# 12-I225_1.net
KiCad netlist of a schematic drawn in Altium Designer
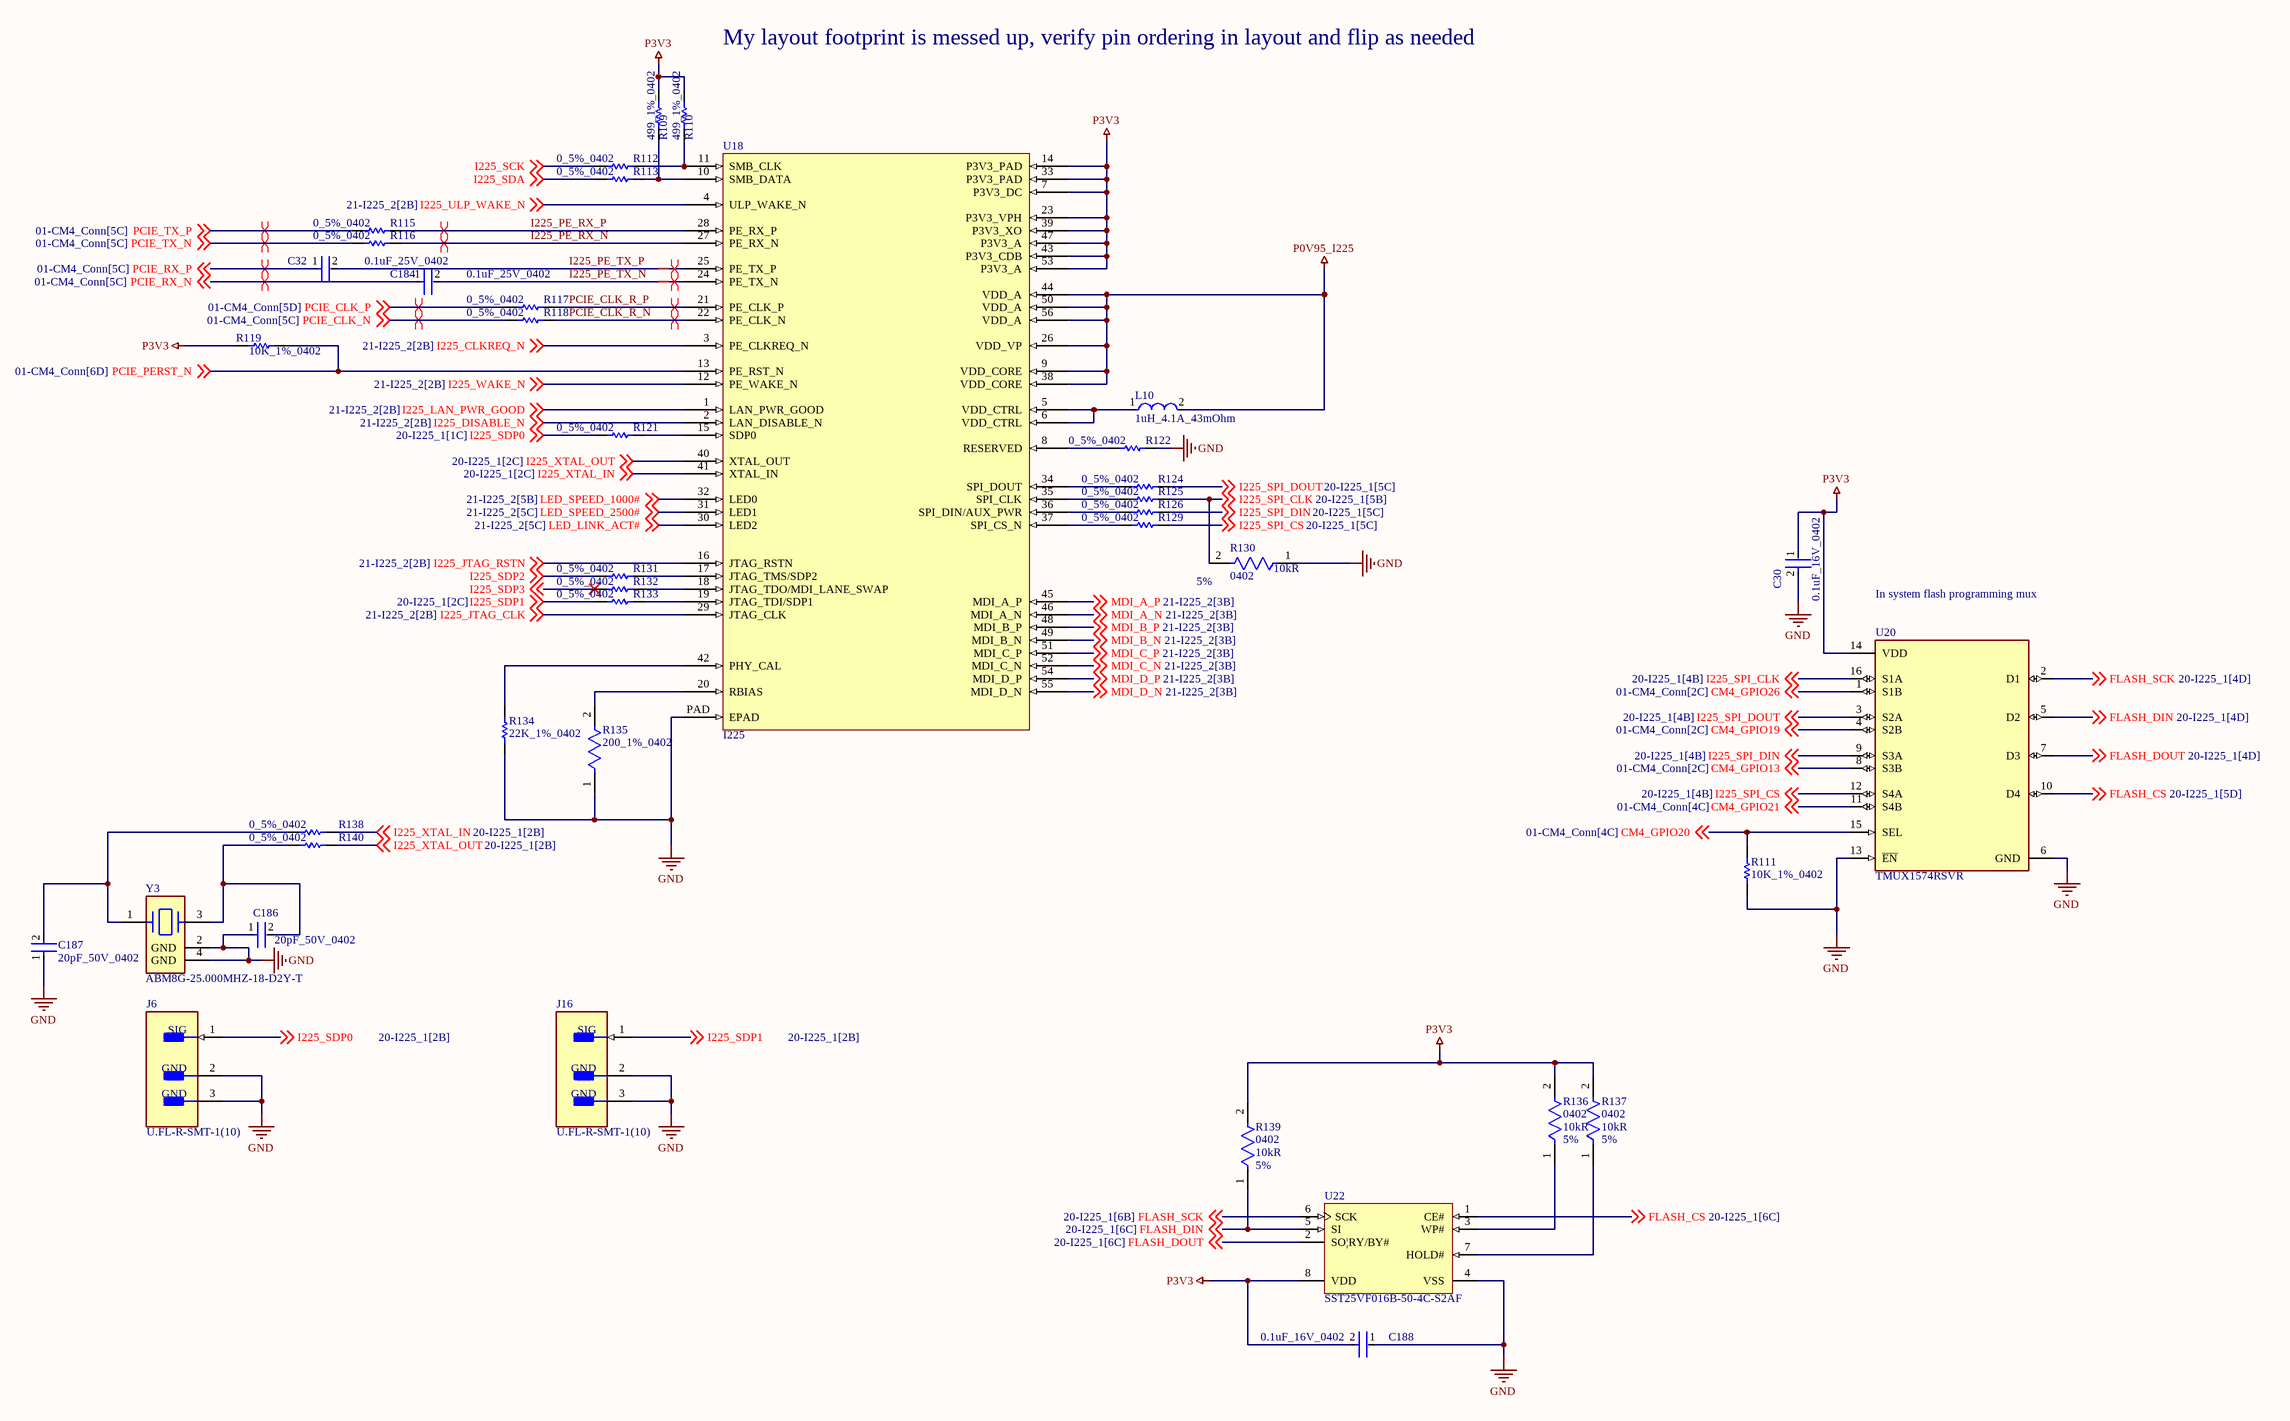
[diagram p0: 12-I225_1.SchDoc]

(export (version "E")
  (design (tool "Eeschema 10.0.6"))
  (components
    (comp (ref "C30")
      (value "0.1uF_16V_0402")
      (footprint "FP-GRM15-MFG")
      (description "CAP CER 0.1UF 16V X7R 0402")
      (fields (field (name "MANUFACTURER PART NUMBER") "GRM155R71C104KA88D") (field (name "TOLERANCE") "10%"))
      (libsource (lib "Altium Content Vault") (part "236180d848d6139a670b325ea6854c9"))
    )
    (comp (ref "C32")
      (value "0.1uF_25V_0402")
      (footprint "FP-0402-L_1_0_1-W_0_5_0_1-IPC_C")
      (description "General Purpose Ceramic Capacitor, 0402, 100nF, 10%, X7R, 15%, 25V")
      (fields (field (name "VOLTAGE") "25V") (field (name "TOLERANCE") "10%"))
      (libsource (lib "Altium Content Vault") (part "b4654b650e69147ec39a6b967a45e02"))
    )
    (comp (ref "C184")
      (value "0.1uF_25V_0402")
      (footprint "FP-0402-L_1_0_1-W_0_5_0_1-IPC_C")
      (description "General Purpose Ceramic Capacitor, 0402, 100nF, 10%, X7R, 15%, 25V")
      (fields (field (name "VOLTAGE") "25V") (field (name "TOLERANCE") "10%"))
      (libsource (lib "Altium Content Vault") (part "b4654b650e69147ec39a6b967a45e02"))
    )
    (comp (ref "C186")
      (value "20pF_50V_0402")
      (footprint "FP-C0402-BB-MFG")
      (description "CAP CER 20PF 50V 5% NP0 0402")
      (fields
        (field (name "MANUFACTURER PART NUMBER") "C0402C200J5GACTU")
        (field (name "OCTOPART") "https://octopart.com/c0402c200j5gactu-kemet-9143900")
      )
      (libsource (lib "Altium Content Vault") (part "b4654b650e69147ec39a6b967a45e02"))
    )
    (comp (ref "C187")
      (value "20pF_50V_0402")
      (footprint "FP-C0402-BB-MFG")
      (description "CAP CER 20PF 50V 5% NP0 0402")
      (fields
        (field (name "MANUFACTURER PART NUMBER") "C0402C200J5GACTU")
        (field (name "OCTOPART") "https://octopart.com/c0402c200j5gactu-kemet-9143900")
      )
      (libsource (lib "Altium Content Vault") (part "b4654b650e69147ec39a6b967a45e02"))
    )
    (comp (ref "C188")
      (value "0.1uF_16V_0402")
      (footprint "FP-GRM15-MFG")
      (description "CAP CER 0.1UF 16V X7R 0402")
      (fields (field (name "MANUFACTURER PART NUMBER") "GRM155R71C104KA88D") (field (name "TOLERANCE") "10%"))
      (libsource (lib "Altium Content Vault") (part "236180d848d6139a670b325ea6854c9"))
    )
    (comp (ref "J6")
      (value "U.FL-R-SMT-1(10)")
      (footprint "FP-U_FL-R-SMT-1_10-MFG")
      (description "CONN U.FL RCPT STR 50 OHM SMD")
      (libsource (lib "Altium Content Vault") (part "7158abf7d987fa84906f6fb0d115710"))
    )
    (comp (ref "J16")
      (value "U.FL-R-SMT-1(10)")
      (footprint "FP-U_FL-R-SMT-1_10-MFG")
      (description "CONN U.FL RCPT STR 50 OHM SMD")
      (libsource (lib "Altium Content Vault") (part "7158abf7d987fa84906f6fb0d115710"))
    )
    (comp (ref "L10")
      (value "1uH_4.1A_43mOhm")
      (footprint "FP-CIGT201610-MFG")
      (description "FIXED IND 1UH 4.1A 43 MOHM SMD")
      (fields (field (name "TOLERANCE") "20%"))
      (libsource (lib "Altium Content Vault") (part "725321dda6339637d4d059423bc1c3c"))
    )
    (comp (ref "R109")
      (value "499_1%_0402")
      (footprint "RESC1005X40X25LL05T05")
      (fields (field (name "MANUFACTURER") "Panasonic") (field (name "PART NUMBER") "ERJ-2RKF4990X"))
      (libsource (lib "Altium Content Vault") (part "RES"))
    )
    (comp (ref "R110")
      (value "499_1%_0402")
      (footprint "RESC1005X40X25LL05T05")
      (fields (field (name "MANUFACTURER") "Panasonic") (field (name "PART NUMBER") "ERJ-2RKF4990X"))
      (libsource (lib "Altium Content Vault") (part "RES"))
    )
    (comp (ref "R111")
      (value "10K_1%_0402")
      (footprint "RESC1005X40X25NL10T10")
      (fields (field (name "MANUFACTURER") "Bourns") (field (name "PART NUMBER") "CR0402-FX-1002GLF"))
      (libsource (lib "Altium Content Vault") (part "RES"))
    )
    (comp (ref "R112")
      (value "0_5%_0402")
      (footprint "RESC1005X40X25LL10T10")
      (fields (field (name "MANUFACTURER") "KOA Speer") (field (name "PART NUMBER") "RK73Z1ETTP"))
      (libsource (lib "Altium Content Vault") (part "RES"))
    )
    (comp (ref "R113")
      (value "0_5%_0402")
      (footprint "RESC1005X40X25LL10T10")
      (fields (field (name "MANUFACTURER") "KOA Speer") (field (name "PART NUMBER") "RK73Z1ETTP"))
      (libsource (lib "Altium Content Vault") (part "RES"))
    )
    (comp (ref "R115")
      (value "0_5%_0402")
      (footprint "RESC1005X40X25LL10T10")
      (fields (field (name "MANUFACTURER") "KOA Speer") (field (name "PART NUMBER") "RK73Z1ETTP"))
      (libsource (lib "Altium Content Vault") (part "RES"))
    )
    (comp (ref "R116")
      (value "0_5%_0402")
      (footprint "RESC1005X40X25LL10T10")
      (fields (field (name "MANUFACTURER") "KOA Speer") (field (name "PART NUMBER") "RK73Z1ETTP"))
      (libsource (lib "Altium Content Vault") (part "RES"))
    )
    (comp (ref "R117")
      (value "0_5%_0402")
      (footprint "RESC1005X40X25LL10T10")
      (fields (field (name "MANUFACTURER") "KOA Speer") (field (name "PART NUMBER") "RK73Z1ETTP"))
      (libsource (lib "Altium Content Vault") (part "RES"))
    )
    (comp (ref "R118")
      (value "0_5%_0402")
      (footprint "RESC1005X40X25LL10T10")
      (fields (field (name "MANUFACTURER") "KOA Speer") (field (name "PART NUMBER") "RK73Z1ETTP"))
      (libsource (lib "Altium Content Vault") (part "RES"))
    )
    (comp (ref "R119")
      (value "10K_1%_0402")
      (footprint "RESC1005X40X25NL10T10")
      (fields (field (name "MANUFACTURER") "Bourns") (field (name "PART NUMBER") "CR0402-FX-1002GLF"))
      (libsource (lib "Altium Content Vault") (part "RES"))
    )
    (comp (ref "R121")
      (value "0_5%_0402")
      (footprint "RESC1005X40X25LL10T10")
      (fields (field (name "MANUFACTURER") "KOA Speer") (field (name "PART NUMBER") "RK73Z1ETTP"))
      (libsource (lib "Altium Content Vault") (part "RES"))
    )
    (comp (ref "R122")
      (value "0_5%_0402")
      (footprint "RESC1005X40X25LL10T10")
      (fields (field (name "MANUFACTURER") "KOA Speer") (field (name "PART NUMBER") "RK73Z1ETTP"))
      (libsource (lib "Altium Content Vault") (part "RES"))
    )
    (comp (ref "R124")
      (value "0_5%_0402")
      (footprint "RESC1005X40X25LL10T10")
      (fields (field (name "MANUFACTURER") "KOA Speer") (field (name "PART NUMBER") "RK73Z1ETTP"))
      (libsource (lib "Altium Content Vault") (part "RES"))
    )
    (comp (ref "R125")
      (value "0_5%_0402")
      (footprint "RESC1005X40X25LL10T10")
      (fields (field (name "MANUFACTURER") "KOA Speer") (field (name "PART NUMBER") "RK73Z1ETTP"))
      (libsource (lib "Altium Content Vault") (part "RES"))
    )
    (comp (ref "R126")
      (value "0_5%_0402")
      (footprint "RESC1005X40X25LL10T10")
      (fields (field (name "MANUFACTURER") "KOA Speer") (field (name "PART NUMBER") "RK73Z1ETTP"))
      (libsource (lib "Altium Content Vault") (part "RES"))
    )
    (comp (ref "R129")
      (value "0_5%_0402")
      (footprint "RESC1005X40X25LL10T10")
      (fields (field (name "MANUFACTURER") "KOA Speer") (field (name "PART NUMBER") "RK73Z1ETTP"))
      (libsource (lib "Altium Content Vault") (part "RES"))
    )
    (comp (ref "R130")
      (value "CRCW040210K0JNED")
      (footprint "FP-CRCW0402-e3-IPC_B")
      (description "RES Thick Film, 10kΩ, 5%, 0.063W, 200ppm/°C, 0402")
      (fields
        (field (name "CASE/PACKAGE") "0402")
        (field (name "RESISTANCE") "10kR")
        (field (name "TOLERANCE") "5%")
      )
      (libsource (lib "Altium Content Vault") (part "1029c3af85768c4190bb7ad29bc67b5"))
    )
    (comp (ref "R131")
      (value "0_5%_0402")
      (footprint "RESC1005X40X25LL10T10")
      (fields (field (name "MANUFACTURER") "KOA Speer") (field (name "PART NUMBER") "RK73Z1ETTP"))
      (libsource (lib "Altium Content Vault") (part "RES"))
    )
    (comp (ref "R132")
      (value "0_5%_0402")
      (footprint "RESC1005X40X25LL10T10")
      (fields (field (name "MANUFACTURER") "KOA Speer") (field (name "PART NUMBER") "RK73Z1ETTP"))
      (libsource (lib "Altium Content Vault") (part "RES"))
    )
    (comp (ref "R133")
      (value "0_5%_0402")
      (footprint "RESC1005X40X25LL10T10")
      (fields (field (name "MANUFACTURER") "KOA Speer") (field (name "PART NUMBER") "RK73Z1ETTP"))
      (libsource (lib "Altium Content Vault") (part "RES"))
    )
    (comp (ref "R134")
      (value "22K_1%_0402")
      (footprint "RESC1005X40X25NL05T05")
      (fields (field (name "PART NUMBER") "CRCW040222K0FKED") (field (name "MANUFACTURER") "Vishay Dale"))
      (libsource (lib "Altium Content Vault") (part "RES"))
    )
    (comp (ref "R135")
      (value "200_1%_0402")
      (footprint "FP-CRCW0402-e3-IPC_C")
      (description "RES Thick Film, 200Ω, 1%, 0.063W, 100ppm/°C, 0402")
      (fields (field (name "TOLERANCE") "1%"))
      (libsource (lib "Altium Content Vault") (part "1029c3af85768c4190bb7ad29bc67b5"))
    )
    (comp (ref "R136")
      (value "CRCW040210K0JNED")
      (footprint "FP-CRCW0402-e3-IPC_B")
      (description "RES Thick Film, 10kΩ, 5%, 0.063W, 200ppm/°C, 0402")
      (fields
        (field (name "CASE/PACKAGE") "0402")
        (field (name "RESISTANCE") "10kR")
        (field (name "TOLERANCE") "5%")
      )
      (libsource (lib "Altium Content Vault") (part "1029c3af85768c4190bb7ad29bc67b5"))
    )
    (comp (ref "R137")
      (value "CRCW040210K0JNED")
      (footprint "FP-CRCW0402-e3-IPC_B")
      (description "RES Thick Film, 10kΩ, 5%, 0.063W, 200ppm/°C, 0402")
      (fields
        (field (name "CASE/PACKAGE") "0402")
        (field (name "RESISTANCE") "10kR")
        (field (name "TOLERANCE") "5%")
      )
      (libsource (lib "Altium Content Vault") (part "1029c3af85768c4190bb7ad29bc67b5"))
    )
    (comp (ref "R138")
      (value "0_5%_0402")
      (footprint "RESC1005X40X25LL10T10")
      (fields (field (name "MANUFACTURER") "KOA Speer") (field (name "PART NUMBER") "RK73Z1ETTP"))
      (libsource (lib "Altium Content Vault") (part "RES"))
    )
    (comp (ref "R139")
      (value "CRCW040210K0JNED")
      (footprint "FP-CRCW0402-e3-IPC_B")
      (description "RES Thick Film, 10kΩ, 5%, 0.063W, 200ppm/°C, 0402")
      (fields
        (field (name "CASE/PACKAGE") "0402")
        (field (name "RESISTANCE") "10kR")
        (field (name "TOLERANCE") "5%")
      )
      (libsource (lib "Altium Content Vault") (part "1029c3af85768c4190bb7ad29bc67b5"))
    )
    (comp (ref "R140")
      (value "0_5%_0402")
      (footprint "RESC1005X40X25LL10T10")
      (fields (field (name "MANUFACTURER") "KOA Speer") (field (name "PART NUMBER") "RK73Z1ETTP"))
      (libsource (lib "Altium Content Vault") (part "RES"))
    )
    (comp (ref "U18") (value "I225") (footprint "I225 QFN56") (libsource (lib "TimeStick_Lib") (part "I225")))
    (comp (ref "U20")
      (value "TMUX1574RSVR")
      (footprint "FP-RSV0016A-MFG")
      (description "IC SWITCH SPDT QUAD 16UQFN")
      (libsource (lib "Altium Content Vault") (part "6ae91f3a9e3ea7621a49082f656dcdc"))
    )
    (comp (ref "U22")
      (value "SST25VF016B-50-4C-S2AF")
      (footprint "MCHP-SOIC-S2A8_M")
      (description "16 Mbit SPI Serial Flash, 2.7 to 3.6 V, 50 MHz, 0 to 70 degC, 8-pin SOIC (S2A8), Tube")
      (fields (field (name "MANUFACTURER") "Microchip"))
      (libsource (lib "Altium Content Vault") (part "MCHP-SST25VFXXXB-SOIX-8"))
    )
    (comp (ref "Y3")
      (value "ABM8G-25.000MHZ-18-D2Y-T")
      (footprint "FP-ABM8G-MFG")
      (description "CRYSTAL 25.0000MHZ 18PF SMD")
      (fields
        (field (name "MANUFACTURER") "Abracon")
        (field (name "OCTOPART") "https://octopart.com/abm8g-25.000mhz-18-d2y-t-abracon-12676602")
      )
      (libsource (lib "Altium Content Vault") (part "82af6c543cb7a88a4cbd02a3a01c293"))
    )
  )
  (nets
    (net (code "1") (name "/I225_PE_RX_N") (class "Default")
      (node (ref "R116") (pin "2") (pinfunction "2_2") (pintype "passive"))
      (node (ref "U18") (pin "27") (pinfunction "PE_RX_N_27") (pintype "input"))
    )
    (net (code "2") (name "/I225_PE_RX_P") (class "Default")
      (node (ref "R115") (pin "2") (pinfunction "2_2") (pintype "passive"))
      (node (ref "U18") (pin "28") (pinfunction "PE_RX_P_28") (pintype "input"))
    )
    (net (code "3") (name "/I225_PE_TX_N") (class "Default")
      (node (ref "C184") (pin "2") (pinfunction "2_2") (pintype "passive"))
      (node (ref "U18") (pin "24") (pinfunction "PE_TX_N_24") (pintype "input"))
    )
    (net (code "4") (name "/I225_PE_TX_P") (class "Default")
      (node (ref "C32") (pin "2") (pinfunction "2_2") (pintype "passive"))
      (node (ref "U18") (pin "25") (pinfunction "PE_TX_P_25") (pintype "input"))
    )
    (net (code "5") (name "/PCIE_CLK_R_N") (class "Default")
      (node (ref "R118") (pin "2") (pinfunction "2_2") (pintype "passive"))
      (node (ref "U18") (pin "22") (pinfunction "PE_CLK_N_22") (pintype "input"))
    )
    (net (code "6") (name "/PCIE_CLK_R_P") (class "Default")
      (node (ref "R117") (pin "2") (pinfunction "2_2") (pintype "passive"))
      (node (ref "U18") (pin "21") (pinfunction "PE_CLK_P_21") (pintype "input"))
    )
    (net (code "7") (name "CM4_GPIO13") (class "Default")
      (node (ref "U20") (pin "8") (pinfunction "S3B_8") (pintype "bidirectional"))
    )
    (net (code "8") (name "CM4_GPIO19") (class "Default")
      (node (ref "U20") (pin "4") (pinfunction "S2B_4") (pintype "bidirectional"))
    )
    (net (code "9") (name "CM4_GPIO20") (class "Default")
      (node (ref "R111") (pin "1") (pinfunction "1_1") (pintype "passive"))
      (node (ref "U20") (pin "15") (pinfunction "SEL_15") (pintype "input"))
    )
    (net (code "10") (name "CM4_GPIO21") (class "Default")
      (node (ref "U20") (pin "11") (pinfunction "S4B_11") (pintype "bidirectional"))
    )
    (net (code "11") (name "CM4_GPIO26") (class "Default")
      (node (ref "U20") (pin "1") (pinfunction "S1B_1") (pintype "bidirectional"))
    )
    (net (code "12") (name "FLASH_CS") (class "Default")
      (node (ref "U20") (pin "10") (pinfunction "D4_10") (pintype "bidirectional"))
      (node (ref "U22") (pin "1") (pinfunction "CE#_1") (pintype "input"))
    )
    (net (code "13") (name "FLASH_DIN") (class "Default")
      (node (ref "R139") (pin "1") (pinfunction "1_1") (pintype "passive"))
      (node (ref "U20") (pin "5") (pinfunction "D2_5") (pintype "bidirectional"))
      (node (ref "U22") (pin "5") (pinfunction "SI_5") (pintype "input"))
    )
    (net (code "14") (name "FLASH_DOUT") (class "Default")
      (node (ref "U20") (pin "7") (pinfunction "D3_7") (pintype "bidirectional"))
      (node (ref "U22") (pin "2") (pinfunction "SO¦RY/BY#_2") (pintype "tri_state"))
    )
    (net (code "15") (name "FLASH_SCK") (class "Default")
      (node (ref "U20") (pin "2") (pinfunction "D1_2") (pintype "bidirectional"))
      (node (ref "U22") (pin "6") (pinfunction "SCK_6") (pintype "input"))
    )
    (net (code "16") (name "GND") (class "Default")
      (node (ref "C186") (pin "1") (pinfunction "1_1") (pintype "passive"))
      (node (ref "C187") (pin "1") (pinfunction "1_1") (pintype "passive"))
      (node (ref "C188") (pin "1") (pinfunction "1_1") (pintype "passive"))
      (node (ref "C30") (pin "2") (pinfunction "2_2") (pintype "passive"))
      (node (ref "J16") (pin "2") (pinfunction "GND_2") (pintype "power_in"))
      (node (ref "J16") (pin "3") (pinfunction "GND_3") (pintype "power_in"))
      (node (ref "J6") (pin "2") (pinfunction "GND_2") (pintype "power_in"))
      (node (ref "J6") (pin "3") (pinfunction "GND_3") (pintype "power_in"))
      (node (ref "R111") (pin "2") (pinfunction "2_2") (pintype "passive"))
      (node (ref "R122") (pin "2") (pinfunction "2_2") (pintype "passive"))
      (node (ref "R130") (pin "1") (pinfunction "1_1") (pintype "passive"))
      (node (ref "R134") (pin "1") (pinfunction "1_1") (pintype "passive"))
      (node (ref "R135") (pin "1") (pinfunction "1_1") (pintype "passive"))
      (node (ref "U18") (pin "PAD") (pinfunction "EPAD_PAD") (pintype "input"))
      (node (ref "U20") (pin "13") (pinfunction "~{EN}_13") (pintype "input"))
      (node (ref "U20") (pin "6") (pinfunction "GND_6") (pintype "power_in"))
      (node (ref "U22") (pin "4") (pinfunction "VSS_4") (pintype "power_in"))
      (node (ref "Y3") (pin "2") (pinfunction "GND_2") (pintype "power_in"))
      (node (ref "Y3") (pin "4") (pinfunction "GND_4") (pintype "power_in"))
    )
    (net (code "17") (name "I225_CLKREQ_N") (class "Default")
      (node (ref "U18") (pin "3") (pinfunction "PE_CLKREQ_N_3") (pintype "input"))
    )
    (net (code "18") (name "I225_DISABLE_N") (class "Default")
      (node (ref "U18") (pin "2") (pinfunction "LAN_DISABLE_N_2") (pintype "input"))
    )
    (net (code "19") (name "I225_JTAG_CLK") (class "Default")
      (node (ref "U18") (pin "29") (pinfunction "JTAG_CLK_29") (pintype "input"))
    )
    (net (code "20") (name "I225_JTAG_RSTN") (class "Default")
      (node (ref "U18") (pin "16") (pinfunction "JTAG_RSTN_16") (pintype "input"))
    )
    (net (code "21") (name "I225_LAN_PWR_GOOD") (class "Default")
      (node (ref "U18") (pin "1") (pinfunction "LAN_PWR_GOOD_1") (pintype "input"))
    )
    (net (code "22") (name "I225_SCK") (class "Default")
      (node (ref "R112") (pin "1") (pinfunction "1_1") (pintype "passive"))
    )
    (net (code "23") (name "I225_SDA") (class "Default")
      (node (ref "R113") (pin "1") (pinfunction "1_1") (pintype "passive"))
    )
    (net (code "24") (name "I225_SDP0") (class "Default")
      (node (ref "J6") (pin "1") (pinfunction "SIG_1") (pintype "input"))
      (node (ref "R121") (pin "1") (pinfunction "1_1") (pintype "passive"))
    )
    (net (code "25") (name "I225_SDP1") (class "Default")
      (node (ref "J16") (pin "1") (pinfunction "SIG_1") (pintype "input"))
      (node (ref "R133") (pin "1") (pinfunction "1_1") (pintype "passive"))
    )
    (net (code "26") (name "I225_SDP2") (class "Default")
      (node (ref "R131") (pin "1") (pinfunction "1_1") (pintype "passive"))
    )
    (net (code "27") (name "I225_SDP3") (class "Default")
      (node (ref "R132") (pin "1") (pinfunction "1_1") (pintype "passive"))
    )
    (net (code "28") (name "I225_SPI_CLK") (class "Default")
      (node (ref "R125") (pin "2") (pinfunction "2_2") (pintype "passive"))
      (node (ref "R130") (pin "2") (pinfunction "2_2") (pintype "passive"))
      (node (ref "U20") (pin "16") (pinfunction "S1A_16") (pintype "bidirectional"))
    )
    (net (code "29") (name "I225_SPI_CS") (class "Default")
      (node (ref "R129") (pin "2") (pinfunction "2_2") (pintype "passive"))
      (node (ref "U20") (pin "12") (pinfunction "S4A_12") (pintype "bidirectional"))
    )
    (net (code "30") (name "I225_SPI_DIN") (class "Default")
      (node (ref "R126") (pin "2") (pinfunction "2_2") (pintype "passive"))
      (node (ref "U20") (pin "9") (pinfunction "S3A_9") (pintype "bidirectional"))
    )
    (net (code "31") (name "I225_SPI_DOUT") (class "Default")
      (node (ref "R124") (pin "2") (pinfunction "2_2") (pintype "passive"))
      (node (ref "U20") (pin "3") (pinfunction "S2A_3") (pintype "bidirectional"))
    )
    (net (code "32") (name "I225_ULP_WAKE_N") (class "Default")
      (node (ref "U18") (pin "4") (pinfunction "ULP_WAKE_N_4") (pintype "input"))
    )
    (net (code "33") (name "I225_WAKE_N") (class "Default")
      (node (ref "U18") (pin "12") (pinfunction "PE_WAKE_N_12") (pintype "input"))
    )
    (net (code "34") (name "I225_XTAL_IN") (class "Default")
      (node (ref "R138") (pin "2") (pinfunction "2_2") (pintype "passive"))
      (node (ref "U18") (pin "41") (pinfunction "XTAL_IN_41") (pintype "input"))
    )
    (net (code "35") (name "I225_XTAL_OUT") (class "Default")
      (node (ref "R140") (pin "2") (pinfunction "2_2") (pintype "passive"))
      (node (ref "U18") (pin "40") (pinfunction "XTAL_OUT_40") (pintype "input"))
    )
    (net (code "36") (name "LED_LINK_ACT#") (class "Default")
      (node (ref "U18") (pin "30") (pinfunction "LED2_30") (pintype "input"))
    )
    (net (code "37") (name "LED_SPEED_1000#") (class "Default")
      (node (ref "U18") (pin "32") (pinfunction "LED0_32") (pintype "input"))
    )
    (net (code "38") (name "LED_SPEED_2500#") (class "Default")
      (node (ref "U18") (pin "31") (pinfunction "LED1_31") (pintype "input"))
    )
    (net (code "39") (name "MDI_A_N") (class "Default")
      (node (ref "U18") (pin "46") (pinfunction "MDI_A_N_46") (pintype "input"))
    )
    (net (code "40") (name "MDI_A_P") (class "Default")
      (node (ref "U18") (pin "45") (pinfunction "MDI_A_P_45") (pintype "input"))
    )
    (net (code "41") (name "MDI_B_N") (class "Default")
      (node (ref "U18") (pin "49") (pinfunction "MDI_B_N_49") (pintype "input"))
    )
    (net (code "42") (name "MDI_B_P") (class "Default")
      (node (ref "U18") (pin "48") (pinfunction "MDI_B_P_48") (pintype "input"))
    )
    (net (code "43") (name "MDI_C_N") (class "Default")
      (node (ref "U18") (pin "52") (pinfunction "MDI_C_N_52") (pintype "input"))
    )
    (net (code "44") (name "MDI_C_P") (class "Default")
      (node (ref "U18") (pin "51") (pinfunction "MDI_C_P_51") (pintype "input"))
    )
    (net (code "45") (name "MDI_D_N") (class "Default")
      (node (ref "U18") (pin "55") (pinfunction "MDI_D_N_55") (pintype "input"))
    )
    (net (code "46") (name "MDI_D_P") (class "Default")
      (node (ref "U18") (pin "54") (pinfunction "MDI_D_P_54") (pintype "input"))
    )
    (net (code "47") (name "Net-(C186-Pad2)") (class "Default")
      (node (ref "C186") (pin "2") (pinfunction "2_2") (pintype "passive"))
      (node (ref "R140") (pin "1") (pinfunction "1_1") (pintype "passive"))
      (node (ref "Y3") (pin "3") (pinfunction "3_3") (pintype "passive"))
    )
    (net (code "48") (name "Net-(C187-Pad2)") (class "Default")
      (node (ref "C187") (pin "2") (pinfunction "2_2") (pintype "passive"))
      (node (ref "R138") (pin "1") (pinfunction "1_1") (pintype "passive"))
      (node (ref "Y3") (pin "1") (pinfunction "1_1") (pintype "passive"))
    )
    (net (code "49") (name "Net-(L10-Pad1)") (class "Default")
      (node (ref "L10") (pin "1") (pinfunction "1_1") (pintype "passive"))
      (node (ref "U18") (pin "5") (pinfunction "VDD_CTRL_5") (pintype "input"))
      (node (ref "U18") (pin "6") (pinfunction "VDD_CTRL_6") (pintype "input"))
    )
    (net (code "50") (name "Net-(U18-JTAG_TDI{slash}SDP1)") (class "Default")
      (node (ref "R133") (pin "2") (pinfunction "2_2") (pintype "passive"))
      (node (ref "U18") (pin "19") (pinfunction "JTAG_TDI/SDP1_19") (pintype "input"))
    )
    (net (code "51") (name "Net-(U18-JTAG_TDO{slash}MDI_LANE_SWAP)") (class "Default")
      (node (ref "R132") (pin "2") (pinfunction "2_2") (pintype "passive"))
      (node (ref "U18") (pin "18") (pinfunction "JTAG_TDO/MDI_LANE_SWAP_18") (pintype "input"))
    )
    (net (code "52") (name "Net-(U18-JTAG_TMS{slash}SDP2)") (class "Default")
      (node (ref "R131") (pin "2") (pinfunction "2_2") (pintype "passive"))
      (node (ref "U18") (pin "17") (pinfunction "JTAG_TMS/SDP2_17") (pintype "input"))
    )
    (net (code "53") (name "Net-(U18-PHY_CAL)") (class "Default")
      (node (ref "R134") (pin "2") (pinfunction "2_2") (pintype "passive"))
      (node (ref "U18") (pin "42") (pinfunction "PHY_CAL_42") (pintype "input"))
    )
    (net (code "54") (name "Net-(U18-RBIAS)") (class "Default")
      (node (ref "R135") (pin "2") (pinfunction "2_2") (pintype "passive"))
      (node (ref "U18") (pin "20") (pinfunction "RBIAS_20") (pintype "input"))
    )
    (net (code "55") (name "Net-(U18-RESERVED)") (class "Default")
      (node (ref "R122") (pin "1") (pinfunction "1_1") (pintype "passive"))
      (node (ref "U18") (pin "8") (pinfunction "RESERVED_8") (pintype "input"))
    )
    (net (code "56") (name "Net-(U18-SDP0)") (class "Default")
      (node (ref "R121") (pin "2") (pinfunction "2_2") (pintype "passive"))
      (node (ref "U18") (pin "15") (pinfunction "SDP0_15") (pintype "input"))
    )
    (net (code "57") (name "Net-(U18-SMB_CLK)") (class "Default")
      (node (ref "R110") (pin "1") (pinfunction "1_1") (pintype "passive"))
      (node (ref "R112") (pin "2") (pinfunction "2_2") (pintype "passive"))
      (node (ref "U18") (pin "11") (pinfunction "SMB_CLK_11") (pintype "input"))
    )
    (net (code "58") (name "Net-(U18-SMB_DATA)") (class "Default")
      (node (ref "R109") (pin "1") (pinfunction "1_1") (pintype "passive"))
      (node (ref "R113") (pin "2") (pinfunction "2_2") (pintype "passive"))
      (node (ref "U18") (pin "10") (pinfunction "SMB_DATA_10") (pintype "input"))
    )
    (net (code "59") (name "Net-(U18-SPI_CLK)") (class "Default")
      (node (ref "R125") (pin "1") (pinfunction "1_1") (pintype "passive"))
      (node (ref "U18") (pin "35") (pinfunction "SPI_CLK_35") (pintype "input"))
    )
    (net (code "60") (name "Net-(U18-SPI_CS_N)") (class "Default")
      (node (ref "R129") (pin "1") (pinfunction "1_1") (pintype "passive"))
      (node (ref "U18") (pin "37") (pinfunction "SPI_CS_N_37") (pintype "input"))
    )
    (net (code "61") (name "Net-(U18-SPI_DIN{slash}AUX_PWR)") (class "Default")
      (node (ref "R126") (pin "1") (pinfunction "1_1") (pintype "passive"))
      (node (ref "U18") (pin "36") (pinfunction "SPI_DIN/AUX_PWR_36") (pintype "input"))
    )
    (net (code "62") (name "Net-(U18-SPI_DOUT)") (class "Default")
      (node (ref "R124") (pin "1") (pinfunction "1_1") (pintype "passive"))
      (node (ref "U18") (pin "34") (pinfunction "SPI_DOUT_34") (pintype "input"))
    )
    (net (code "63") (name "Net-(U22-HOLD#)") (class "Default")
      (node (ref "R137") (pin "1") (pinfunction "1_1") (pintype "passive"))
      (node (ref "U22") (pin "7") (pinfunction "HOLD#_7") (pintype "input"))
    )
    (net (code "64") (name "Net-(U22-WP#)") (class "Default")
      (node (ref "R136") (pin "1") (pinfunction "1_1") (pintype "passive"))
      (node (ref "U22") (pin "3") (pinfunction "WP#_3") (pintype "input"))
    )
    (net (code "65") (name "P0V95_I225") (class "Default")
      (node (ref "L10") (pin "2") (pinfunction "2_2") (pintype "passive"))
      (node (ref "U18") (pin "26") (pinfunction "VDD_VP_26") (pintype "input"))
      (node (ref "U18") (pin "38") (pinfunction "VDD_CORE_38") (pintype "input"))
      (node (ref "U18") (pin "44") (pinfunction "VDD_A_44") (pintype "input"))
      (node (ref "U18") (pin "50") (pinfunction "VDD_A_50") (pintype "input"))
      (node (ref "U18") (pin "56") (pinfunction "VDD_A_56") (pintype "input"))
      (node (ref "U18") (pin "9") (pinfunction "VDD_CORE_9") (pintype "input"))
    )
    (net (code "66") (name "P3V3") (class "Default")
      (node (ref "C188") (pin "2") (pinfunction "2_2") (pintype "passive"))
      (node (ref "C30") (pin "1") (pinfunction "1_1") (pintype "passive"))
      (node (ref "R109") (pin "2") (pinfunction "2_2") (pintype "passive"))
      (node (ref "R110") (pin "2") (pinfunction "2_2") (pintype "passive"))
      (node (ref "R119") (pin "2") (pinfunction "2_2") (pintype "passive"))
      (node (ref "R136") (pin "2") (pinfunction "2_2") (pintype "passive"))
      (node (ref "R137") (pin "2") (pinfunction "2_2") (pintype "passive"))
      (node (ref "R139") (pin "2") (pinfunction "2_2") (pintype "passive"))
      (node (ref "U18") (pin "14") (pinfunction "P3V3_PAD_14") (pintype "input"))
      (node (ref "U18") (pin "23") (pinfunction "P3V3_VPH_23") (pintype "input"))
      (node (ref "U18") (pin "33") (pinfunction "P3V3_PAD_33") (pintype "input"))
      (node (ref "U18") (pin "39") (pinfunction "P3V3_XO_39") (pintype "input"))
      (node (ref "U18") (pin "43") (pinfunction "P3V3_CDB_43") (pintype "input"))
      (node (ref "U18") (pin "47") (pinfunction "P3V3_A_47") (pintype "input"))
      (node (ref "U18") (pin "53") (pinfunction "P3V3_A_53") (pintype "input"))
      (node (ref "U18") (pin "7") (pinfunction "P3V3_DC_7") (pintype "input"))
      (node (ref "U20") (pin "14") (pinfunction "VDD_14") (pintype "power_in"))
      (node (ref "U22") (pin "8") (pinfunction "VDD_8") (pintype "power_in"))
    )
    (net (code "67") (name "PCIE_CLK_N") (class "Default")
      (node (ref "R118") (pin "1") (pinfunction "1_1") (pintype "passive"))
    )
    (net (code "68") (name "PCIE_CLK_P") (class "Default")
      (node (ref "R117") (pin "1") (pinfunction "1_1") (pintype "passive"))
    )
    (net (code "69") (name "PCIE_PERST_N") (class "Default")
      (node (ref "R119") (pin "1") (pinfunction "1_1") (pintype "passive"))
      (node (ref "U18") (pin "13") (pinfunction "PE_RST_N_13") (pintype "input"))
    )
    (net (code "70") (name "PCIE_RX_N") (class "Default")
      (node (ref "C184") (pin "1") (pinfunction "1_1") (pintype "passive"))
    )
    (net (code "71") (name "PCIE_RX_P") (class "Default")
      (node (ref "C32") (pin "1") (pinfunction "1_1") (pintype "passive"))
    )
    (net (code "72") (name "PCIE_TX_N") (class "Default")
      (node (ref "R116") (pin "1") (pinfunction "1_1") (pintype "passive"))
    )
    (net (code "73") (name "PCIE_TX_P") (class "Default")
      (node (ref "R115") (pin "1") (pinfunction "1_1") (pintype "passive"))
    )
  )
)
